# power.net
KiCad netlist of a schematic drawn in Altium Designer
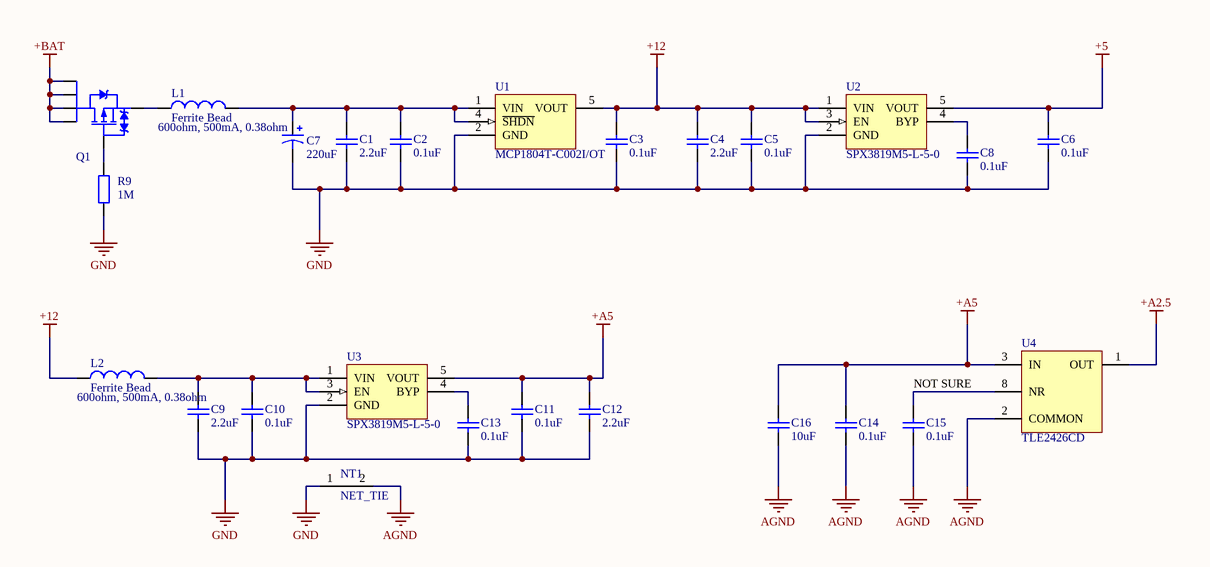
[diagram p0: power.SchDoc]

(export (version "E")
  (design (tool "Eeschema 10.0.6"))
  (components
    (comp (ref "C1")
      (value "2.2uF")
      (footprint "C0805")
      (description "Capacitor")
      (fields (field (name "Comment") "Cap") (field (name "PUBLISHER") "Altium Limited"))
      (libsource (lib "Miscellaneous Devices") (part "Cap"))
    )
    (comp (ref "C2")
      (value "0.1uF")
      (footprint "C0805")
      (description "Capacitor")
      (fields (field (name "Comment") "Cap") (field (name "PUBLISHER") "Altium Limited"))
      (libsource (lib "Miscellaneous Devices") (part "Cap"))
    )
    (comp (ref "C3")
      (value "0.1uF")
      (footprint "C0805")
      (description "Capacitor")
      (fields (field (name "Comment") "Cap") (field (name "PUBLISHER") "Altium Limited"))
      (libsource (lib "Miscellaneous Devices") (part "Cap"))
    )
    (comp (ref "C4")
      (value "2.2uF")
      (footprint "C0805")
      (description "Capacitor")
      (fields (field (name "Comment") "Cap") (field (name "PUBLISHER") "Altium Limited"))
      (libsource (lib "Miscellaneous Devices") (part "Cap"))
    )
    (comp (ref "C5")
      (value "0.1uF")
      (footprint "C0805")
      (description "Capacitor")
      (fields (field (name "Comment") "Cap") (field (name "PUBLISHER") "Altium Limited"))
      (libsource (lib "Miscellaneous Devices") (part "Cap"))
    )
    (comp (ref "C6")
      (value "0.1uF")
      (footprint "C0805")
      (description "Capacitor")
      (fields (field (name "Comment") "Cap") (field (name "PUBLISHER") "Altium Limited"))
      (libsource (lib "Miscellaneous Devices") (part "Cap"))
    )
    (comp (ref "C7")
      (value "220uF")
      (footprint "EEUFM1V221L")
      (description "Polarized Capacitor (Radial)")
      (fields (field (name "Comment") "Cap Pol1") (field (name "PUBLISHER") "Altium Limited"))
      (libsource (lib "Miscellaneous Devices") (part "Cap Pol1"))
    )
    (comp (ref "C8")
      (value "0.1uF")
      (footprint "C0805")
      (description "Capacitor")
      (fields (field (name "Comment") "Cap") (field (name "PUBLISHER") "Altium Limited"))
      (libsource (lib "Miscellaneous Devices") (part "Cap"))
    )
    (comp (ref "C9")
      (value "2.2uF")
      (footprint "C0805")
      (description "Capacitor")
      (fields (field (name "Comment") "Cap") (field (name "PUBLISHER") "Altium Limited"))
      (libsource (lib "Miscellaneous Devices") (part "Cap"))
    )
    (comp (ref "C10")
      (value "0.1uF")
      (footprint "C0805")
      (description "Capacitor")
      (fields (field (name "Comment") "Cap") (field (name "PUBLISHER") "Altium Limited"))
      (libsource (lib "Miscellaneous Devices") (part "Cap"))
    )
    (comp (ref "C11")
      (value "0.1uF")
      (footprint "C0805")
      (description "Capacitor")
      (fields (field (name "Comment") "Cap") (field (name "PUBLISHER") "Altium Limited"))
      (libsource (lib "Miscellaneous Devices") (part "Cap"))
    )
    (comp (ref "C12")
      (value "2.2uF")
      (footprint "C0805")
      (description "Capacitor")
      (fields (field (name "Comment") "Cap") (field (name "PUBLISHER") "Altium Limited"))
      (libsource (lib "Miscellaneous Devices") (part "Cap"))
    )
    (comp (ref "C13")
      (value "0.1uF")
      (footprint "C0805")
      (description "Capacitor")
      (fields (field (name "Comment") "Cap") (field (name "PUBLISHER") "Altium Limited"))
      (libsource (lib "Miscellaneous Devices") (part "Cap"))
    )
    (comp (ref "C14")
      (value "0.1uF")
      (footprint "C0805")
      (description "Capacitor")
      (fields (field (name "Comment") "Cap") (field (name "PUBLISHER") "Altium Limited"))
      (libsource (lib "Miscellaneous Devices") (part "Cap"))
    )
    (comp (ref "C15")
      (value "0.1uF")
      (footprint "C0805")
      (description "Capacitor")
      (fields (field (name "Comment") "Cap") (field (name "PUBLISHER") "Altium Limited"))
      (libsource (lib "Miscellaneous Devices") (part "Cap"))
    )
    (comp (ref "C16")
      (value "10uF")
      (footprint "C0805")
      (description "Capacitor")
      (fields (field (name "Comment") "Cap") (field (name "PUBLISHER") "Altium Limited"))
      (libsource (lib "Miscellaneous Devices") (part "Cap"))
    )
    (comp (ref "L1")
      (value "Ferrite Bead")
      (footprint "BLM18AG221SN1D")
      (description "Inductor")
      (fields
        (field (name "ALTIUM_VALUE") "600ohm, 500mA, 0.38ohm")
        (field (name "PUBLISHER") "Altium Limited")
      )
      (libsource (lib "Miscellaneous Devices") (part "Inductor"))
    )
    (comp (ref "L2")
      (value "Ferrite Bead")
      (footprint "BLM18AG221SN1D")
      (description "Inductor")
      (fields
        (field (name "ALTIUM_VALUE") "600ohm, 500mA, 0.38ohm")
        (field (name "PUBLISHER") "Altium Limited")
      )
      (libsource (lib "Miscellaneous Devices") (part "Inductor"))
    )
    (comp (ref "NT1")
      (value "NET_TIE")
      (footprint "NETTIE")
      (libsource (lib "hydrophone preamp") (part "NET_TIE"))
    )
    (comp (ref "Q1")
      (value "PMOSFET_P")
      (footprint "FDC608PZ")
      (description "FAIRCHILD SEMICONDUCTOR - FDC608PZ - MOSFET, P, SMD, SSOT-6")
      (libsource (lib "hydrophone preamp") (part "PMOSFET_P"))
    )
    (comp (ref "R9")
      (value "1M")
      (footprint "R0603")
      (description "Resistor")
      (fields (field (name "Comment") "Res2") (field (name "PUBLISHER") "Altium Limited"))
      (libsource (lib "Miscellaneous Devices") (part "Res2"))
    )
    (comp (ref "U1")
      (value "MCP1804T-C002I/OT")
      (footprint "MCP1804T-C002I/OT")
      (description "MICROCHIP - MCP1804T-C002I/OT - IC, LDO, 12V, 150MA, 5SOT23")
      (libsource (lib "hydrophone preamp") (part "MCP1804T-C002I/OT"))
    )
    (comp (ref "U2")
      (value "SPX3819M5-L-5-0")
      (footprint "SPX3819M5-L-5-0")
      (description "EXAR - SPX3819M5-L-5-0 - LDO, 500MA, 5V, LOW NOISE, 5SOT23")
      (libsource (lib "hydrophone preamp") (part "SPX3819M5-L-5-0"))
    )
    (comp (ref "U3")
      (value "SPX3819M5-L-5-0")
      (footprint "SPX3819M5-L-5-0")
      (description "EXAR - SPX3819M5-L-5-0 - LDO, 500MA, 5V, LOW NOISE, 5SOT23")
      (libsource (lib "hydrophone preamp") (part "SPX3819M5-L-5-0"))
    )
    (comp (ref "U4")
      (value "TLE2426CD")
      (footprint "TLE2426CD")
      (description "TEXAS INSTRUMENTS - TLE2426CD - VIRTUAL GROUND REFERENCE, SMD, 2426")
      (libsource (lib "hydrophone preamp") (part "TLE2426CD"))
    )
  )
  (nets
    (net (code "1") (name "+5") (class "Default")
      (node (ref "C6") (pin "2") (pinfunction "2_2") (pintype "passive"))
      (node (ref "U2") (pin "5") (pinfunction "VOUT_5") (pintype "power_in"))
    )
    (net (code "2") (name "+12") (class "Default")
      (node (ref "C3") (pin "2") (pinfunction "2_2") (pintype "passive"))
      (node (ref "C4") (pin "2") (pinfunction "2_2") (pintype "passive"))
      (node (ref "C5") (pin "2") (pinfunction "2_2") (pintype "passive"))
      (node (ref "L2") (pin "1") (pinfunction "1_1") (pintype "passive"))
      (node (ref "U1") (pin "5") (pinfunction "VOUT_5") (pintype "power_in"))
      (node (ref "U2") (pin "1") (pinfunction "VIN_1") (pintype "power_in"))
      (node (ref "U2") (pin "3") (pinfunction "EN_3") (pintype "input"))
    )
    (net (code "3") (name "+A2.5") (class "Default")
      (node (ref "U4") (pin "1") (pinfunction "OUT_1") (pintype "passive"))
    )
    (net (code "4") (name "+A5") (class "Default")
      (node (ref "C11") (pin "2") (pinfunction "2_2") (pintype "passive"))
      (node (ref "C12") (pin "2") (pinfunction "2_2") (pintype "passive"))
      (node (ref "C14") (pin "2") (pinfunction "2_2") (pintype "passive"))
      (node (ref "C16") (pin "2") (pinfunction "2_2") (pintype "passive"))
      (node (ref "U3") (pin "5") (pinfunction "VOUT_5") (pintype "power_in"))
      (node (ref "U4") (pin "3") (pinfunction "IN_3") (pintype "power_in"))
    )
    (net (code "5") (name "+BAT") (class "Default")
      (node (ref "Q1") (pin "1") (pinfunction "D_1") (pintype "passive"))
      (node (ref "Q1") (pin "2") (pinfunction "D_2") (pintype "passive"))
      (node (ref "Q1") (pin "5") (pinfunction "D_5") (pintype "passive"))
      (node (ref "Q1") (pin "6") (pinfunction "D_6") (pintype "passive"))
    )
    (net (code "6") (name "AGND") (class "Default")
      (node (ref "C14") (pin "1") (pinfunction "1_1") (pintype "passive"))
      (node (ref "C15") (pin "1") (pinfunction "1_1") (pintype "passive"))
      (node (ref "C16") (pin "1") (pinfunction "1_1") (pintype "passive"))
      (node (ref "NT1") (pin "2") (pinfunction "2_2") (pintype "passive"))
      (node (ref "U4") (pin "2") (pinfunction "COMMON_2") (pintype "power_in"))
    )
    (net (code "7") (name "GND") (class "Default")
      (node (ref "C1") (pin "1") (pinfunction "1_1") (pintype "passive"))
      (node (ref "C10") (pin "1") (pinfunction "1_1") (pintype "passive"))
      (node (ref "C11") (pin "1") (pinfunction "1_1") (pintype "passive"))
      (node (ref "C12") (pin "1") (pinfunction "1_1") (pintype "passive"))
      (node (ref "C13") (pin "1") (pinfunction "1_1") (pintype "passive"))
      (node (ref "C2") (pin "1") (pinfunction "1_1") (pintype "passive"))
      (node (ref "C3") (pin "1") (pinfunction "1_1") (pintype "passive"))
      (node (ref "C4") (pin "1") (pinfunction "1_1") (pintype "passive"))
      (node (ref "C5") (pin "1") (pinfunction "1_1") (pintype "passive"))
      (node (ref "C6") (pin "1") (pinfunction "1_1") (pintype "passive"))
      (node (ref "C7") (pin "2") (pinfunction "2_2") (pintype "passive"))
      (node (ref "C8") (pin "1") (pinfunction "1_1") (pintype "passive"))
      (node (ref "C9") (pin "1") (pinfunction "1_1") (pintype "passive"))
      (node (ref "NT1") (pin "1") (pinfunction "1_1") (pintype "passive"))
      (node (ref "R9") (pin "1") (pinfunction "1_1") (pintype "passive"))
      (node (ref "U1") (pin "2") (pinfunction "GND_2") (pintype "power_in"))
      (node (ref "U2") (pin "2") (pinfunction "GND_2") (pintype "power_in"))
      (node (ref "U3") (pin "2") (pinfunction "GND_2") (pintype "power_in"))
    )
    (net (code "8") (name "Net-(Q1-G)") (class "Default")
      (node (ref "Q1") (pin "3") (pinfunction "G_3") (pintype "passive"))
      (node (ref "R9") (pin "2") (pinfunction "2_2") (pintype "passive"))
    )
    (net (code "9") (name "Net-(Q1-S)") (class "Default")
      (node (ref "L1") (pin "1") (pinfunction "1_1") (pintype "passive"))
      (node (ref "Q1") (pin "4") (pinfunction "S_4") (pintype "passive"))
    )
    (net (code "10") (name "Net-(U1-VIN)") (class "Default")
      (node (ref "C1") (pin "2") (pinfunction "2_2") (pintype "passive"))
      (node (ref "C2") (pin "2") (pinfunction "2_2") (pintype "passive"))
      (node (ref "C7") (pin "1") (pinfunction "1_1") (pintype "passive"))
      (node (ref "L1") (pin "2") (pinfunction "2_2") (pintype "passive"))
      (node (ref "U1") (pin "1") (pinfunction "VIN_1") (pintype "power_in"))
      (node (ref "U1") (pin "4") (pinfunction "~{SHDN}_4") (pintype "input"))
    )
    (net (code "11") (name "Net-(U2-BYP)") (class "Default")
      (node (ref "C8") (pin "2") (pinfunction "2_2") (pintype "passive"))
      (node (ref "U2") (pin "4") (pinfunction "BYP_4") (pintype "passive"))
    )
    (net (code "12") (name "Net-(U3-BYP)") (class "Default")
      (node (ref "C13") (pin "2") (pinfunction "2_2") (pintype "passive"))
      (node (ref "U3") (pin "4") (pinfunction "BYP_4") (pintype "passive"))
    )
    (net (code "13") (name "Net-(U3-EN)") (class "Default")
      (node (ref "C10") (pin "2") (pinfunction "2_2") (pintype "passive"))
      (node (ref "C9") (pin "2") (pinfunction "2_2") (pintype "passive"))
      (node (ref "L2") (pin "2") (pinfunction "2_2") (pintype "passive"))
      (node (ref "U3") (pin "1") (pinfunction "VIN_1") (pintype "power_in"))
      (node (ref "U3") (pin "3") (pinfunction "EN_3") (pintype "input"))
    )
    (net (code "14") (name "Net-(U4-NR)") (class "Default")
      (node (ref "C15") (pin "2") (pinfunction "2_2") (pintype "passive"))
      (node (ref "U4") (pin "8") (pinfunction "NR_8") (pintype "passive"))
    )
  )
)
